# LED_Button.net
KiCad netlist of a schematic drawn in Altium Designer
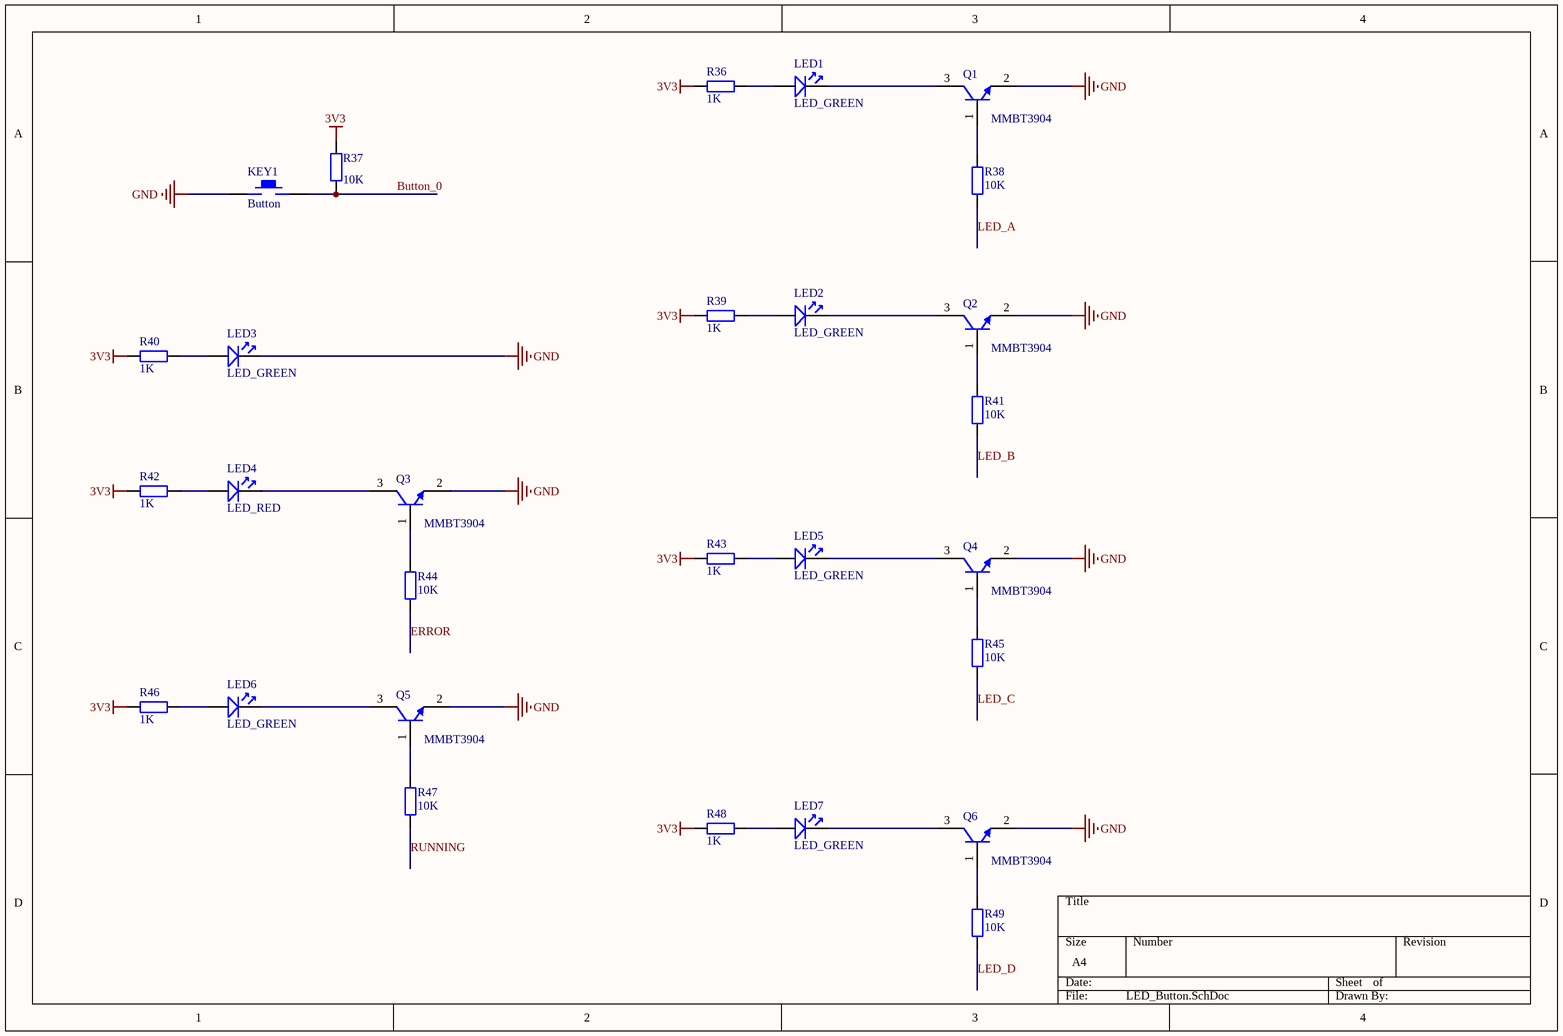
[diagram p0: LED_Button.SchDoc]

(export (version "E")
  (design (tool "Eeschema 10.0.6"))
  (components
    (comp (ref "KEY1")
      (value "Button")
      (footprint "KEY_SOP324225")
      (libsource (lib "ZYNQ_开发板") (part "KEY_M"))
    )
    (comp (ref "LED1") (value "LED_GREEN") (footprint "LED 0603R") (libsource (lib "ZYNQ_开发板") (part "LED")))
    (comp (ref "LED2") (value "LED_GREEN") (footprint "LED 0603R") (libsource (lib "ZYNQ_开发板") (part "LED")))
    (comp (ref "LED3") (value "LED_GREEN") (footprint "LED 0603R") (libsource (lib "ZYNQ_开发板") (part "LED")))
    (comp (ref "LED4") (value "LED_RED") (footprint "LED 0603R") (libsource (lib "ZYNQ_开发板") (part "LED")))
    (comp (ref "LED5") (value "LED_GREEN") (footprint "LED 0603R") (libsource (lib "ZYNQ_开发板") (part "LED")))
    (comp (ref "LED6") (value "LED_GREEN") (footprint "LED 0603R") (libsource (lib "ZYNQ_开发板") (part "LED")))
    (comp (ref "LED7") (value "LED_GREEN") (footprint "LED 0603R") (libsource (lib "ZYNQ_开发板") (part "LED")))
    (comp (ref "Q1")
      (value "MMBT3904")
      (footprint "FAIR-SOT23-3_V")
      (description "NPN General Purpose Amplifier, 40 V, 0.2 A, -55 to 150 degC, 3-Pin SOT23, RoHS, Tape and Reel")
      (fields (field (name "TOLERANCE") "30ppm"))
      (libsource (lib "Altium Content Vault") (part "BJT-NPN-BEC-3"))
    )
    (comp (ref "Q2")
      (value "MMBT3904")
      (footprint "FAIR-SOT23-3_V")
      (description "NPN General Purpose Amplifier, 40 V, 0.2 A, -55 to 150 degC, 3-Pin SOT23, RoHS, Tape and Reel")
      (fields (field (name "TOLERANCE") "30ppm"))
      (libsource (lib "Altium Content Vault") (part "BJT-NPN-BEC-3"))
    )
    (comp (ref "Q3")
      (value "MMBT3904")
      (footprint "FAIR-SOT23-3_V")
      (description "NPN General Purpose Amplifier, 40 V, 0.2 A, -55 to 150 degC, 3-Pin SOT23, RoHS, Tape and Reel")
      (fields (field (name "TOLERANCE") "30ppm"))
      (libsource (lib "Altium Content Vault") (part "BJT-NPN-BEC-3"))
    )
    (comp (ref "Q4")
      (value "MMBT3904")
      (footprint "FAIR-SOT23-3_V")
      (description "NPN General Purpose Amplifier, 40 V, 0.2 A, -55 to 150 degC, 3-Pin SOT23, RoHS, Tape and Reel")
      (fields (field (name "TOLERANCE") "30ppm"))
      (libsource (lib "Altium Content Vault") (part "BJT-NPN-BEC-3"))
    )
    (comp (ref "Q5")
      (value "MMBT3904")
      (footprint "FAIR-SOT23-3_V")
      (description "NPN General Purpose Amplifier, 40 V, 0.2 A, -55 to 150 degC, 3-Pin SOT23, RoHS, Tape and Reel")
      (fields (field (name "TOLERANCE") "30ppm"))
      (libsource (lib "Altium Content Vault") (part "BJT-NPN-BEC-3"))
    )
    (comp (ref "Q6")
      (value "MMBT3904")
      (footprint "FAIR-SOT23-3_V")
      (description "NPN General Purpose Amplifier, 40 V, 0.2 A, -55 to 150 degC, 3-Pin SOT23, RoHS, Tape and Reel")
      (fields (field (name "TOLERANCE") "30ppm"))
      (libsource (lib "Altium Content Vault") (part "BJT-NPN-BEC-3"))
    )
    (comp (ref "R36")
      (value "1K")
      (footprint "R 0402_L")
      (description "贴片电阻")
      (fields (field (name "版权归属") "源创客"))
      (libsource (lib "ZYNQ_开发板") (part "R_1"))
    )
    (comp (ref "R37")
      (value "10K")
      (footprint "R 0402_L")
      (description "贴片电阻")
      (fields (field (name "版权归属") "源创客"))
      (libsource (lib "ZYNQ_开发板") (part "R_1"))
    )
    (comp (ref "R38")
      (value "10K")
      (footprint "R 0402_L")
      (description "贴片电阻")
      (fields (field (name "版权归属") "源创客"))
      (libsource (lib "ZYNQ_开发板") (part "R_1"))
    )
    (comp (ref "R39")
      (value "1K")
      (footprint "R 0402_L")
      (description "贴片电阻")
      (fields (field (name "版权归属") "源创客"))
      (libsource (lib "ZYNQ_开发板") (part "R_1"))
    )
    (comp (ref "R40")
      (value "1K")
      (footprint "R 0402_L")
      (description "贴片电阻")
      (fields (field (name "版权归属") "源创客"))
      (libsource (lib "ZYNQ_开发板") (part "R_1"))
    )
    (comp (ref "R41")
      (value "10K")
      (footprint "R 0402_L")
      (description "贴片电阻")
      (fields (field (name "版权归属") "源创客"))
      (libsource (lib "ZYNQ_开发板") (part "R_1"))
    )
    (comp (ref "R42")
      (value "1K")
      (footprint "R 0402_L")
      (description "贴片电阻")
      (fields (field (name "版权归属") "源创客"))
      (libsource (lib "ZYNQ_开发板") (part "R_1"))
    )
    (comp (ref "R43")
      (value "1K")
      (footprint "R 0402_L")
      (description "贴片电阻")
      (fields (field (name "版权归属") "源创客"))
      (libsource (lib "ZYNQ_开发板") (part "R_1"))
    )
    (comp (ref "R44")
      (value "10K")
      (footprint "R 0402_L")
      (description "贴片电阻")
      (fields (field (name "版权归属") "源创客"))
      (libsource (lib "ZYNQ_开发板") (part "R_1"))
    )
    (comp (ref "R45")
      (value "10K")
      (footprint "R 0402_L")
      (description "贴片电阻")
      (fields (field (name "版权归属") "源创客"))
      (libsource (lib "ZYNQ_开发板") (part "R_1"))
    )
    (comp (ref "R46")
      (value "1K")
      (footprint "R 0402_L")
      (description "贴片电阻")
      (fields (field (name "版权归属") "源创客"))
      (libsource (lib "ZYNQ_开发板") (part "R_1"))
    )
    (comp (ref "R47")
      (value "10K")
      (footprint "R 0402_L")
      (description "贴片电阻")
      (fields (field (name "版权归属") "源创客"))
      (libsource (lib "ZYNQ_开发板") (part "R_1"))
    )
    (comp (ref "R48")
      (value "1K")
      (footprint "R 0402_L")
      (description "贴片电阻")
      (fields (field (name "版权归属") "源创客"))
      (libsource (lib "ZYNQ_开发板") (part "R_1"))
    )
    (comp (ref "R49")
      (value "10K")
      (footprint "R 0402_L")
      (description "贴片电阻")
      (fields (field (name "版权归属") "源创客"))
      (libsource (lib "ZYNQ_开发板") (part "R_1"))
    )
  )
  (nets
    (net (code "1") (name "/Button_0") (class "Default")
      (node (ref "KEY1") (pin "2") (pinfunction "2_2") (pintype "passive"))
      (node (ref "R37") (pin "1") (pinfunction "1_1") (pintype "passive"))
    )
    (net (code "2") (name "/ERROR") (class "Default")
      (node (ref "R44") (pin "1") (pinfunction "1_1") (pintype "passive"))
    )
    (net (code "3") (name "/LED_A") (class "Default")
      (node (ref "R38") (pin "1") (pinfunction "1_1") (pintype "passive"))
    )
    (net (code "4") (name "/LED_B") (class "Default")
      (node (ref "R41") (pin "1") (pinfunction "1_1") (pintype "passive"))
    )
    (net (code "5") (name "/LED_C") (class "Default")
      (node (ref "R45") (pin "1") (pinfunction "1_1") (pintype "passive"))
    )
    (net (code "6") (name "/LED_D") (class "Default")
      (node (ref "R49") (pin "1") (pinfunction "1_1") (pintype "passive"))
    )
    (net (code "7") (name "/RUNNING") (class "Default")
      (node (ref "R47") (pin "1") (pinfunction "1_1") (pintype "passive"))
    )
    (net (code "8") (name "3V3") (class "Default")
      (node (ref "R36") (pin "1") (pinfunction "1_1") (pintype "passive"))
      (node (ref "R37") (pin "2") (pinfunction "2_2") (pintype "passive"))
      (node (ref "R39") (pin "1") (pinfunction "1_1") (pintype "passive"))
      (node (ref "R40") (pin "1") (pinfunction "1_1") (pintype "passive"))
      (node (ref "R42") (pin "1") (pinfunction "1_1") (pintype "passive"))
      (node (ref "R43") (pin "1") (pinfunction "1_1") (pintype "passive"))
      (node (ref "R46") (pin "1") (pinfunction "1_1") (pintype "passive"))
      (node (ref "R48") (pin "1") (pinfunction "1_1") (pintype "passive"))
    )
    (net (code "9") (name "GND") (class "Default")
      (node (ref "KEY1") (pin "1") (pinfunction "1_1") (pintype "passive"))
      (node (ref "LED3") (pin "2") (pinfunction "2_2") (pintype "passive"))
      (node (ref "Q1") (pin "2") (pinfunction "E_2") (pintype "passive"))
      (node (ref "Q2") (pin "2") (pinfunction "E_2") (pintype "passive"))
      (node (ref "Q3") (pin "2") (pinfunction "E_2") (pintype "passive"))
      (node (ref "Q4") (pin "2") (pinfunction "E_2") (pintype "passive"))
      (node (ref "Q5") (pin "2") (pinfunction "E_2") (pintype "passive"))
      (node (ref "Q6") (pin "2") (pinfunction "E_2") (pintype "passive"))
    )
    (net (code "10") (name "Net-(LED1-Pad1)") (class "Default")
      (node (ref "LED1") (pin "1") (pinfunction "1_1") (pintype "passive"))
      (node (ref "R36") (pin "2") (pinfunction "2_2") (pintype "passive"))
    )
    (net (code "11") (name "Net-(LED2-Pad1)") (class "Default")
      (node (ref "LED2") (pin "1") (pinfunction "1_1") (pintype "passive"))
      (node (ref "R39") (pin "2") (pinfunction "2_2") (pintype "passive"))
    )
    (net (code "12") (name "Net-(LED3-Pad1)") (class "Default")
      (node (ref "LED3") (pin "1") (pinfunction "1_1") (pintype "passive"))
      (node (ref "R40") (pin "2") (pinfunction "2_2") (pintype "passive"))
    )
    (net (code "13") (name "Net-(LED4-Pad1)") (class "Default")
      (node (ref "LED4") (pin "1") (pinfunction "1_1") (pintype "passive"))
      (node (ref "R42") (pin "2") (pinfunction "2_2") (pintype "passive"))
    )
    (net (code "14") (name "Net-(LED5-Pad1)") (class "Default")
      (node (ref "LED5") (pin "1") (pinfunction "1_1") (pintype "passive"))
      (node (ref "R43") (pin "2") (pinfunction "2_2") (pintype "passive"))
    )
    (net (code "15") (name "Net-(LED6-Pad1)") (class "Default")
      (node (ref "LED6") (pin "1") (pinfunction "1_1") (pintype "passive"))
      (node (ref "R46") (pin "2") (pinfunction "2_2") (pintype "passive"))
    )
    (net (code "16") (name "Net-(LED7-Pad1)") (class "Default")
      (node (ref "LED7") (pin "1") (pinfunction "1_1") (pintype "passive"))
      (node (ref "R48") (pin "2") (pinfunction "2_2") (pintype "passive"))
    )
    (net (code "17") (name "Net-(Q1-B)") (class "Default")
      (node (ref "Q1") (pin "1") (pinfunction "B_1") (pintype "passive"))
      (node (ref "R38") (pin "2") (pinfunction "2_2") (pintype "passive"))
    )
    (net (code "18") (name "Net-(Q1-C)") (class "Default")
      (node (ref "LED1") (pin "2") (pinfunction "2_2") (pintype "passive"))
      (node (ref "Q1") (pin "3") (pinfunction "C_3") (pintype "passive"))
    )
    (net (code "19") (name "Net-(Q2-B)") (class "Default")
      (node (ref "Q2") (pin "1") (pinfunction "B_1") (pintype "passive"))
      (node (ref "R41") (pin "2") (pinfunction "2_2") (pintype "passive"))
    )
    (net (code "20") (name "Net-(Q2-C)") (class "Default")
      (node (ref "LED2") (pin "2") (pinfunction "2_2") (pintype "passive"))
      (node (ref "Q2") (pin "3") (pinfunction "C_3") (pintype "passive"))
    )
    (net (code "21") (name "Net-(Q3-B)") (class "Default")
      (node (ref "Q3") (pin "1") (pinfunction "B_1") (pintype "passive"))
      (node (ref "R44") (pin "2") (pinfunction "2_2") (pintype "passive"))
    )
    (net (code "22") (name "Net-(Q3-C)") (class "Default")
      (node (ref "LED4") (pin "2") (pinfunction "2_2") (pintype "passive"))
      (node (ref "Q3") (pin "3") (pinfunction "C_3") (pintype "passive"))
    )
    (net (code "23") (name "Net-(Q4-B)") (class "Default")
      (node (ref "Q4") (pin "1") (pinfunction "B_1") (pintype "passive"))
      (node (ref "R45") (pin "2") (pinfunction "2_2") (pintype "passive"))
    )
    (net (code "24") (name "Net-(Q4-C)") (class "Default")
      (node (ref "LED5") (pin "2") (pinfunction "2_2") (pintype "passive"))
      (node (ref "Q4") (pin "3") (pinfunction "C_3") (pintype "passive"))
    )
    (net (code "25") (name "Net-(Q5-B)") (class "Default")
      (node (ref "Q5") (pin "1") (pinfunction "B_1") (pintype "passive"))
      (node (ref "R47") (pin "2") (pinfunction "2_2") (pintype "passive"))
    )
    (net (code "26") (name "Net-(Q5-C)") (class "Default")
      (node (ref "LED6") (pin "2") (pinfunction "2_2") (pintype "passive"))
      (node (ref "Q5") (pin "3") (pinfunction "C_3") (pintype "passive"))
    )
    (net (code "27") (name "Net-(Q6-B)") (class "Default")
      (node (ref "Q6") (pin "1") (pinfunction "B_1") (pintype "passive"))
      (node (ref "R49") (pin "2") (pinfunction "2_2") (pintype "passive"))
    )
    (net (code "28") (name "Net-(Q6-C)") (class "Default")
      (node (ref "LED7") (pin "2") (pinfunction "2_2") (pintype "passive"))
      (node (ref "Q6") (pin "3") (pinfunction "C_3") (pintype "passive"))
    )
  )
)
